# Projet_travelling_detecteur_V3.net
KiCad netlist of a schematic drawn in Altium Designer
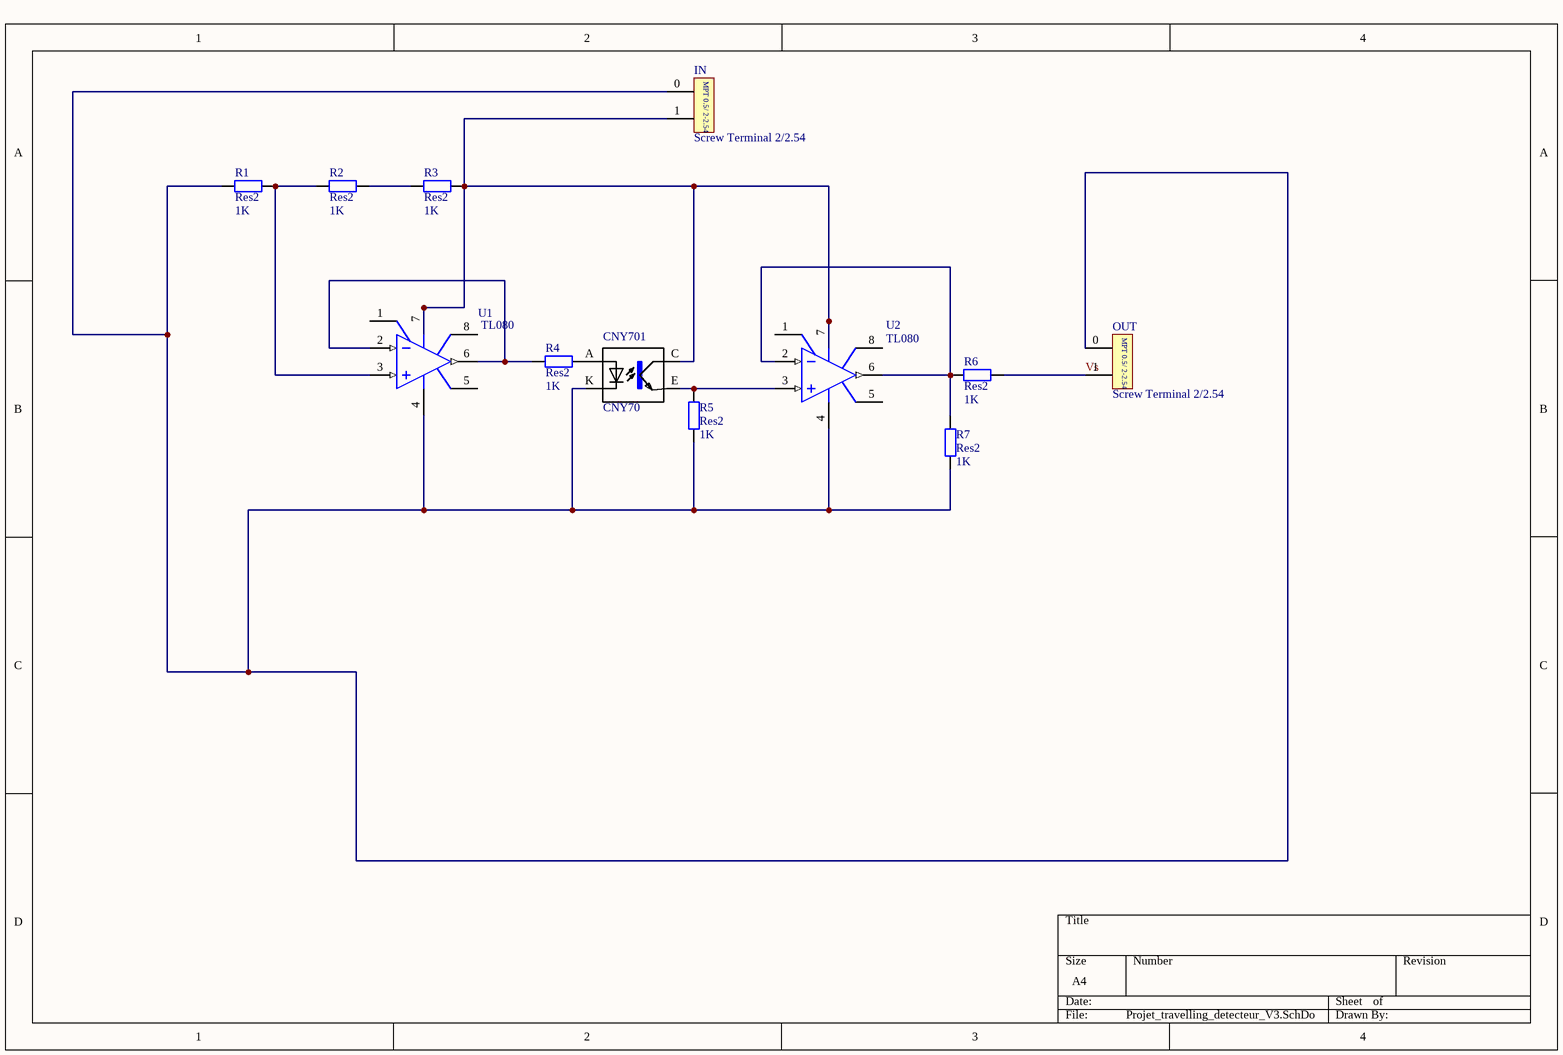
[diagram p0: Projet_travelling_detecteur_V3.SchDoc]

(export (version "E")
  (design (tool "Eeschema 10.0.6"))
  (components
    (comp (ref "CNY701")
      (value "CNY70")
      (footprint "*4_CNY70(Primary)")
      (description "Reflective Optical Sensor 0.197 _5mm_ PCB Mount")
      (fields (field (name "MF") "Vishay"))
      (libsource (lib "CNY70") (part "CNY70"))
    )
    (comp (ref "IN")
      (value "Screw Terminal 2/2.54")
      (footprint "MPT_0.5-2-2.54")
      (description "MPT 0.5/ 2 contacts / 2.54 mm")
      (libsource (lib "Library_Polytech_Connector") (part "Screw Terminal 2/2.54"))
    )
    (comp (ref "OUT")
      (value "Screw Terminal 2/2.54")
      (footprint "MPT_0.5-2-2.54")
      (description "MPT 0.5/ 2 contacts / 2.54 mm")
      (libsource (lib "Library_Polytech_Connector") (part "Screw Terminal 2/2.54"))
    )
    (comp (ref "R1")
      (value "Res2")
      (footprint "AXIAL-0.4")
      (description "Resistor")
      (fields (field (name "ALTIUM_VALUE") "1K") (field (name "PUBLISHER") "Altium Limited"))
      (libsource (lib "Miscellaneous Devices") (part "Res2"))
    )
    (comp (ref "R2")
      (value "Res2")
      (footprint "AXIAL-0.4")
      (description "Resistor")
      (fields (field (name "ALTIUM_VALUE") "1K") (field (name "PUBLISHER") "Altium Limited"))
      (libsource (lib "Miscellaneous Devices") (part "Res2"))
    )
    (comp (ref "R3")
      (value "Res2")
      (footprint "AXIAL-0.4")
      (description "Resistor")
      (fields (field (name "ALTIUM_VALUE") "1K") (field (name "PUBLISHER") "Altium Limited"))
      (libsource (lib "Miscellaneous Devices") (part "Res2"))
    )
    (comp (ref "R4")
      (value "Res2")
      (footprint "AXIAL-0.4")
      (description "Resistor")
      (fields (field (name "ALTIUM_VALUE") "1K") (field (name "PUBLISHER") "Altium Limited"))
      (libsource (lib "Miscellaneous Devices") (part "Res2"))
    )
    (comp (ref "R5")
      (value "Res2")
      (footprint "AXIAL-0.4")
      (description "Resistor")
      (fields (field (name "ALTIUM_VALUE") "1K") (field (name "PUBLISHER") "Altium Limited"))
      (libsource (lib "") (part "Res2_2"))
    )
    (comp (ref "R6")
      (value "Res2")
      (footprint "AXIAL-0.4")
      (description "Resistor")
      (fields (field (name "ALTIUM_VALUE") "1K") (field (name "PUBLISHER") "Altium Limited"))
      (libsource (lib "Miscellaneous Devices") (part "Res2"))
    )
    (comp (ref "R7")
      (value "Res2")
      (footprint "AXIAL-0.4")
      (description "Resistor")
      (fields (field (name "ALTIUM_VALUE") "1K") (field (name "PUBLISHER") "Altium Limited"))
      (libsource (lib "") (part "Res2_1"))
    )
    (comp (ref "U1")
      (value "TL080")
      (footprint "DIL 8")
      (description "JFET-Input Operational Amplifier")
      (fields (field (name "PUBLISHER") "Altium Limited"))
      (libsource (lib "Library_Polytech_Actif") (part "TL080"))
    )
    (comp (ref "U2")
      (value "TL080")
      (footprint "DIL 8")
      (description "JFET-Input Operational Amplifier")
      (fields (field (name "PUBLISHER") "Altium Limited"))
      (libsource (lib "Library_Polytech_Actif") (part "TL080"))
    )
  )
  (nets
    (net (code "1") (name "/Vs") (class "Default")
      (node (ref "OUT") (pin "1") (pinfunction "1_1") (pintype "passive"))
      (node (ref "R6") (pin "2") (pinfunction "2_2") (pintype "passive"))
    )
    (net (code "2") (name "Net-(CNY701-C)") (class "Default")
      (node (ref "CNY701") (pin "K") (pinfunction "C_K") (pintype "passive"))
      (node (ref "IN") (pin "0") (pinfunction "0_0") (pintype "passive"))
      (node (ref "OUT") (pin "0") (pinfunction "0_0") (pintype "passive"))
      (node (ref "R1") (pin "1") (pinfunction "1_1") (pintype "passive"))
      (node (ref "R5") (pin "2") (pinfunction "2_2") (pintype "passive"))
      (node (ref "R7") (pin "1") (pinfunction "1_1") (pintype "passive"))
      (node (ref "U1") (pin "4") (pinfunction "V-_4") (pintype "power_in"))
      (node (ref "U2") (pin "4") (pinfunction "V-_4") (pintype "power_in"))
    )
    (net (code "3") (name "Net-(CNY701-COL)") (class "Default")
      (node (ref "CNY701") (pin "C") (pinfunction "COL_C") (pintype "passive"))
      (node (ref "IN") (pin "1") (pinfunction "1_1") (pintype "passive"))
      (node (ref "R3") (pin "2") (pinfunction "2_2") (pintype "passive"))
      (node (ref "U1") (pin "7") (pinfunction "V+_7") (pintype "power_in"))
      (node (ref "U2") (pin "7") (pinfunction "V+_7") (pintype "power_in"))
    )
    (net (code "4") (name "Net-(CNY701-EMI)") (class "Default")
      (node (ref "CNY701") (pin "E") (pinfunction "EMI_E") (pintype "passive"))
      (node (ref "R5") (pin "1") (pinfunction "1_1") (pintype "passive"))
      (node (ref "U2") (pin "3") (pinfunction "IN+_3") (pintype "input"))
    )
    (net (code "5") (name "Net-(CNY701-PadA)") (class "Default")
      (node (ref "CNY701") (pin "A") (pinfunction "A_A") (pintype "passive"))
      (node (ref "R4") (pin "2") (pinfunction "2_2") (pintype "passive"))
    )
    (net (code "6") (name "Net-(R2-Pad2)") (class "Default")
      (node (ref "R2") (pin "2") (pinfunction "2_2") (pintype "passive"))
      (node (ref "R3") (pin "1") (pinfunction "1_1") (pintype "passive"))
    )
    (net (code "7") (name "Net-(U1-IN+)") (class "Default")
      (node (ref "R1") (pin "2") (pinfunction "2_2") (pintype "passive"))
      (node (ref "R2") (pin "1") (pinfunction "1_1") (pintype "passive"))
      (node (ref "U1") (pin "3") (pinfunction "IN+_3") (pintype "input"))
    )
    (net (code "8") (name "Net-(U1-IN-)") (class "Default")
      (node (ref "R4") (pin "1") (pinfunction "1_1") (pintype "passive"))
      (node (ref "U1") (pin "2") (pinfunction "IN-_2") (pintype "input"))
      (node (ref "U1") (pin "6") (pinfunction "OUT_6") (pintype "output"))
    )
    (net (code "9") (name "Net-(U2-IN-)") (class "Default")
      (node (ref "R6") (pin "1") (pinfunction "1_1") (pintype "passive"))
      (node (ref "R7") (pin "2") (pinfunction "2_2") (pintype "passive"))
      (node (ref "U2") (pin "2") (pinfunction "IN-_2") (pintype "input"))
      (node (ref "U2") (pin "6") (pinfunction "OUT_6") (pintype "output"))
    )
    (net (code "10") (name "unconnected-(U1-BAL1{slash}CMPEN-Pad1)") (class "Default")
      (node (ref "U1") (pin "1") (pinfunction "BAL1/CMPEN_1") (pintype "passive"))
    )
    (net (code "11") (name "unconnected-(U1-BAL2-Pad5)") (class "Default")
      (node (ref "U1") (pin "5") (pinfunction "BAL2_5") (pintype "passive"))
    )
    (net (code "12") (name "unconnected-(U1-CMPEN-Pad8)") (class "Default")
      (node (ref "U1") (pin "8") (pinfunction "CMPEN_8") (pintype "passive"))
    )
    (net (code "13") (name "unconnected-(U2-BAL1{slash}CMPEN-Pad1)") (class "Default")
      (node (ref "U2") (pin "1") (pinfunction "BAL1/CMPEN_1") (pintype "passive"))
    )
    (net (code "14") (name "unconnected-(U2-BAL2-Pad5)") (class "Default")
      (node (ref "U2") (pin "5") (pinfunction "BAL2_5") (pintype "passive"))
    )
    (net (code "15") (name "unconnected-(U2-CMPEN-Pad8)") (class "Default")
      (node (ref "U2") (pin "8") (pinfunction "CMPEN_8") (pintype "passive"))
    )
  )
)
